# 6_Power_distribution_II.net
KiCad netlist of a schematic drawn in Altium Designer
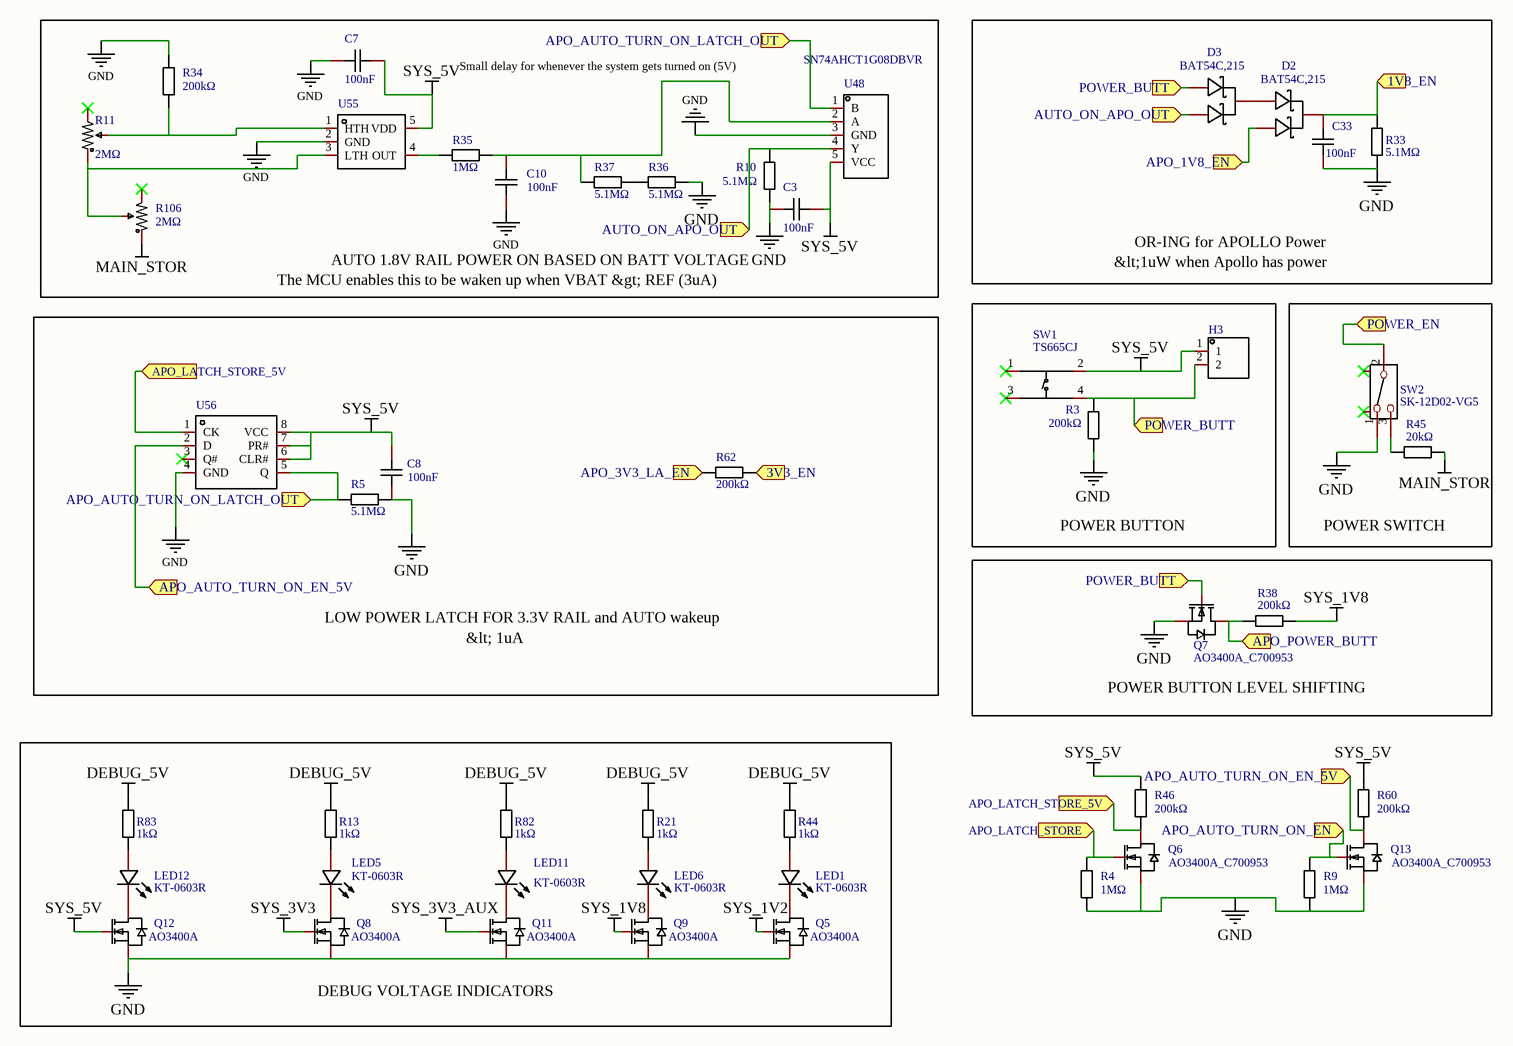
[diagram p0: 6_Power distribution II.schdoc]

(export (version "E")
  (design (tool "Eeschema 10.0.6"))
  (components
    (comp (ref "C3")
      (value "100nF")
      (fields
        (field (name "NAME") "100nF")
        (field (name "MANUFACTURER") "YAGEO")
        (field (name "MANUFACTURER PART") "CC0603KRX7R9BB104")
      )
      (libsource (lib "altium-import") (part "root_0_CC0603KRX7R9BB104_"))
    )
    (comp (ref "C7")
      (value "100nF")
      (fields
        (field (name "NAME") "100nF")
        (field (name "MANUFACTURER") "YAGEO")
        (field (name "MANUFACTURER PART") "CC0603KRX7R9BB104")
      )
      (libsource (lib "altium-import") (part "root_0_CC0603KRX7R9BB104_"))
    )
    (comp (ref "C8")
      (value "100nF")
      (fields
        (field (name "NAME") "100nF")
        (field (name "MANUFACTURER") "YAGEO")
        (field (name "MANUFACTURER PART") "CC0603KRX7R9BB104")
      )
      (libsource (lib "altium-import") (part "root_3_CC0603KRX7R9BB104_"))
    )
    (comp (ref "C10")
      (value "100nF")
      (fields
        (field (name "NAME") "100nF")
        (field (name "MANUFACTURER") "YAGEO")
        (field (name "MANUFACTURER PART") "CC0603KRX7R9BB104")
      )
      (libsource (lib "altium-import") (part "root_1_CC0603KRX7R9BB104_"))
    )
    (comp (ref "C33")
      (value "100nF")
      (fields
        (field (name "NAME") "100nF")
        (field (name "MANUFACTURER") "YAGEO")
        (field (name "MANUFACTURER PART") "CC0603KRX7R9BB104")
      )
      (libsource (lib "altium-import") (part "root_3_CC0603KRX7R9BB104_"))
    )
    (comp (ref "D2")
      (value "BAT54C,215")
      (fields (field (name "NAME") "BAT54C,215") (field (name "MANUFACTURER") "Nexperia"))
      (libsource (lib "altium-import") (part "root_0_BAT54C,215_"))
    )
    (comp (ref "D3")
      (value "BAT54C,215")
      (fields (field (name "NAME") "BAT54C,215") (field (name "MANUFACTURER") "Nexperia"))
      (libsource (lib "altium-import") (part "root_0_BAT54C,215_"))
    )
    (comp (ref "H3")
      (value "HDR-M_2.54_1x2P")
      (libsource (lib "altium-import") (part "root_0_HDR-M_2.54_1x2P_"))
    )
    (comp (ref "LED1")
      (value "KT-0603R")
      (fields (field (name "NAME") "KT-0603R") (field (name "MANUFACTURER") "KENTO"))
      (libsource (lib "altium-import") (part "root_1_KT-0603R_"))
    )
    (comp (ref "LED5")
      (value "KT-0603R")
      (fields (field (name "NAME") "KT-0603R") (field (name "MANUFACTURER") "KENTO"))
      (libsource (lib "altium-import") (part "root_1_KT-0603R_"))
    )
    (comp (ref "LED6")
      (value "KT-0603R")
      (fields (field (name "NAME") "KT-0603R") (field (name "MANUFACTURER") "KENTO"))
      (libsource (lib "altium-import") (part "root_1_KT-0603R_"))
    )
    (comp (ref "LED11")
      (value "KT-0603R")
      (fields (field (name "NAME") "KT-0603R") (field (name "MANUFACTURER") "KENTO"))
      (libsource (lib "altium-import") (part "root_1_KT-0603R_"))
    )
    (comp (ref "LED12")
      (value "KT-0603R")
      (fields (field (name "NAME") "KT-0603R") (field (name "MANUFACTURER") "KENTO"))
      (libsource (lib "altium-import") (part "root_1_KT-0603R_"))
    )
    (comp (ref "Q5")
      (value "AO3400A")
      (fields (field (name "NAME") "AO3400A") (field (name "MANUFACTURER") "HUASHUO(华朔)"))
      (libsource (lib "altium-import") (part "root_0_AO3400A_"))
    )
    (comp (ref "Q6")
      (value "AO3400A_C700953")
      (fields
        (field (name "NAME") "AO3400A_C700953")
        (field (name "MANUFACTURER") "HUASHUO(华朔)")
        (field (name "MANUFACTURER PART") "AO3400A")
      )
      (libsource (lib "altium-import") (part "root_0_AO3400A_"))
    )
    (comp (ref "Q7")
      (value "AO3400A_C700953")
      (fields
        (field (name "NAME") "AO3400A_C700953")
        (field (name "MANUFACTURER") "HUASHUO(华朔)")
        (field (name "MANUFACTURER PART") "AO3400A")
      )
      (libsource (lib "altium-import") (part "root_3_AO3400A_"))
    )
    (comp (ref "Q8")
      (value "AO3400A")
      (fields (field (name "NAME") "AO3400A") (field (name "MANUFACTURER") "HUASHUO(华朔)"))
      (libsource (lib "altium-import") (part "root_0_AO3400A_"))
    )
    (comp (ref "Q9")
      (value "AO3400A")
      (fields (field (name "NAME") "AO3400A") (field (name "MANUFACTURER") "HUASHUO(华朔)"))
      (libsource (lib "altium-import") (part "root_0_AO3400A_"))
    )
    (comp (ref "Q11")
      (value "AO3400A")
      (fields (field (name "NAME") "AO3400A") (field (name "MANUFACTURER") "HUASHUO(华朔)"))
      (libsource (lib "altium-import") (part "root_0_AO3400A_"))
    )
    (comp (ref "Q12")
      (value "AO3400A")
      (fields (field (name "NAME") "AO3400A") (field (name "MANUFACTURER") "HUASHUO(华朔)"))
      (libsource (lib "altium-import") (part "root_0_AO3400A_"))
    )
    (comp (ref "Q13")
      (value "AO3400A_C700953")
      (fields
        (field (name "NAME") "AO3400A_C700953")
        (field (name "MANUFACTURER") "HUASHUO(华朔)")
        (field (name "MANUFACTURER PART") "AO3400A")
      )
      (libsource (lib "altium-import") (part "root_0_AO3400A_"))
    )
    (comp (ref "R3")
      (value "200kΩ")
      (fields
        (field (name "NAME") "200kΩ")
        (field (name "MANUFACTURER") "UniOhm")
        (field (name "MANUFACTURER PART") "0603WAF2003T5E")
      )
      (libsource (lib "altium-import") (part "root_1_0603WAF2003T5E_"))
    )
    (comp (ref "R4")
      (value "1MΩ")
      (fields
        (field (name "NAME") "1MΩ")
        (field (name "MANUFACTURER") "UniOhm")
        (field (name "MANUFACTURER PART") "0603WAF1004T5E")
      )
      (libsource (lib "altium-import") (part "root_3_0603WAF1004T5E_"))
    )
    (comp (ref "R5")
      (value "5.1MΩ")
      (fields
        (field (name "NAME") "5.1MΩ")
        (field (name "MANUFACTURER") "UniOhm")
        (field (name "MANUFACTURER PART") "0603WAF5104T5E")
      )
      (libsource (lib "altium-import") (part "root_2_0603WAF5104T5E_"))
    )
    (comp (ref "R9")
      (value "1MΩ")
      (fields
        (field (name "NAME") "1MΩ")
        (field (name "MANUFACTURER") "UniOhm")
        (field (name "MANUFACTURER PART") "0603WAF1004T5E")
      )
      (libsource (lib "altium-import") (part "root_3_0603WAF1004T5E_"))
    )
    (comp (ref "R10")
      (value "5.1MΩ")
      (fields
        (field (name "NAME") "5.1MΩ")
        (field (name "MANUFACTURER") "UniOhm")
        (field (name "MANUFACTURER PART") "0603WAF5104T5E")
      )
      (libsource (lib "altium-import") (part "root_1_0603WAF5104T5E_"))
    )
    (comp (ref "R11")
      (value "2MΩ")
      (description "Resistance: Tolerance:±10% Tolerance:±10%")
      (fields (field (name "MANUFACTURER") "BOURNS") (field (name "MANUFACTURER PART") "3386P-1-205LF"))
      (libsource (lib "altium-import") (part "root_3_3386P-1-205LF_"))
    )
    (comp (ref "R13")
      (value "1kΩ")
      (fields
        (field (name "NAME") "1kΩ")
        (field (name "MANUFACTURER") "UniOhm")
        (field (name "MANUFACTURER PART") "0603WAF1001T5E")
      )
      (libsource (lib "altium-import") (part "root_1_0603WAF1001T5E_"))
    )
    (comp (ref "R21")
      (value "1kΩ")
      (fields
        (field (name "NAME") "1kΩ")
        (field (name "MANUFACTURER") "UniOhm")
        (field (name "MANUFACTURER PART") "0603WAF1001T5E")
      )
      (libsource (lib "altium-import") (part "root_1_0603WAF1001T5E_"))
    )
    (comp (ref "R33")
      (value "5.1MΩ")
      (fields
        (field (name "NAME") "5.1MΩ")
        (field (name "MANUFACTURER") "UniOhm")
        (field (name "MANUFACTURER PART") "0603WAF5104T5E")
      )
      (libsource (lib "altium-import") (part "root_1_0603WAF5104T5E_"))
    )
    (comp (ref "R34")
      (value "200kΩ")
      (fields
        (field (name "NAME") "200kΩ")
        (field (name "MANUFACTURER") "UniOhm")
        (field (name "MANUFACTURER PART") "0603WAF2003T5E")
      )
      (libsource (lib "altium-import") (part "root_3_0603WAF2003T5E_"))
    )
    (comp (ref "R35")
      (value "1MΩ")
      (fields
        (field (name "NAME") "1MΩ")
        (field (name "MANUFACTURER") "UniOhm")
        (field (name "MANUFACTURER PART") "0603WAF1004T5E")
      )
      (libsource (lib "altium-import") (part "root_2_0603WAF1004T5E_"))
    )
    (comp (ref "R36")
      (value "5.1MΩ")
      (fields
        (field (name "NAME") "5.1MΩ")
        (field (name "MANUFACTURER") "UniOhm")
        (field (name "MANUFACTURER PART") "0603WAF5104T5E")
      )
      (libsource (lib "altium-import") (part "root_2_0603WAF5104T5E_"))
    )
    (comp (ref "R37")
      (value "5.1MΩ")
      (fields
        (field (name "NAME") "5.1MΩ")
        (field (name "MANUFACTURER") "UniOhm")
        (field (name "MANUFACTURER PART") "0603WAF5104T5E")
      )
      (libsource (lib "altium-import") (part "root_2_0603WAF5104T5E_"))
    )
    (comp (ref "R38")
      (value "200kΩ")
      (fields
        (field (name "NAME") "200kΩ")
        (field (name "MANUFACTURER") "UniOhm")
        (field (name "MANUFACTURER PART") "0603WAF2003T5E")
      )
      (libsource (lib "altium-import") (part "root_2_0603WAF2003T5E_"))
    )
    (comp (ref "R44")
      (value "1kΩ")
      (fields
        (field (name "NAME") "1kΩ")
        (field (name "MANUFACTURER") "UniOhm")
        (field (name "MANUFACTURER PART") "0603WAF1001T5E")
      )
      (libsource (lib "altium-import") (part "root_1_0603WAF1001T5E_"))
    )
    (comp (ref "R45")
      (value "20kΩ")
      (fields
        (field (name "NAME") "20kΩ")
        (field (name "MANUFACTURER") "UniOhm")
        (field (name "MANUFACTURER PART") "0603WAF2002T5E")
      )
      (libsource (lib "altium-import") (part "root_2_0603WAF2002T5E_"))
    )
    (comp (ref "R46")
      (value "200kΩ")
      (fields
        (field (name "NAME") "200kΩ")
        (field (name "MANUFACTURER") "UniOhm")
        (field (name "MANUFACTURER PART") "0603WAF2003T5E")
      )
      (libsource (lib "altium-import") (part "root_3_0603WAF2003T5E_"))
    )
    (comp (ref "R60")
      (value "200kΩ")
      (fields
        (field (name "NAME") "200kΩ")
        (field (name "MANUFACTURER") "UniOhm")
        (field (name "MANUFACTURER PART") "0603WAF2003T5E")
      )
      (libsource (lib "altium-import") (part "root_3_0603WAF2003T5E_"))
    )
    (comp (ref "R62")
      (value "200kΩ")
      (fields
        (field (name "NAME") "200kΩ")
        (field (name "MANUFACTURER") "UniOhm")
        (field (name "MANUFACTURER PART") "0603WAF2003T5E")
      )
      (libsource (lib "altium-import") (part "root_0_0603WAF2003T5E_"))
    )
    (comp (ref "R82")
      (value "1kΩ")
      (fields
        (field (name "NAME") "1kΩ")
        (field (name "MANUFACTURER") "UniOhm")
        (field (name "MANUFACTURER PART") "0603WAF1001T5E")
      )
      (libsource (lib "altium-import") (part "root_1_0603WAF1001T5E_"))
    )
    (comp (ref "R83")
      (value "1kΩ")
      (fields
        (field (name "NAME") "1kΩ")
        (field (name "MANUFACTURER") "UniOhm")
        (field (name "MANUFACTURER PART") "0603WAF1001T5E")
      )
      (libsource (lib "altium-import") (part "root_1_0603WAF1001T5E_"))
    )
    (comp (ref "R106")
      (value "2MΩ")
      (description "Resistance: Tolerance:±10% Tolerance:±10%")
      (fields (field (name "MANUFACTURER") "BOURNS") (field (name "MANUFACTURER PART") "3386P-1-205LF"))
      (libsource (lib "altium-import") (part "root_3_mirrored_3386P-1-205LF_"))
    )
    (comp (ref "SW1")
      (value "TS665CJ")
      (fields (field (name "NAME") "TS665CJ") (field (name "MANUFACTURER") "SHOU HAN"))
      (libsource (lib "altium-import") (part "root_0_TS665CJ_"))
    )
    (comp (ref "SW2")
      (value "SK-12D02-VG5")
      (fields
        (field (name "NAME") "SK-12D02-VG5")
        (field (name "MANUFACTURER") "Rectangular Connectors - Contacts")
      )
      (libsource (lib "altium-import") (part "root_3_SK-12D02-VG5_"))
    )
    (comp (ref "U48")
      (value "SN74AHCT1G08DBVR_C113521")
      (fields (field (name "MANUFACTURER") "TI(德州仪器)") (field (name "MANUFACTURER PART") "SN74AHCT1G08DBVR"))
      (libsource (lib "altium-import") (part "root_0_SN74AHCT1G08DBVR_C113521_"))
    )
    (comp (ref "U55")
      (value "MIC841HYC5-TR")
      (fields (field (name "MANUFACTURER") "MICROCHIP(美国微芯)"))
      (libsource (lib "altium-import") (part "root_0_MIC841HYC5-TR_"))
    )
    (comp (ref "U56")
      (value "TC7W74FU,LF")
      (fields (field (name "MANUFACTURER") "TOSHIBA(东芝)"))
      (libsource (lib "altium-import") (part "root_0_TC7W74FU,LF_"))
    )
  )
  (nets
    (net (code "1") (name "/1V8_EN") (class "Default")
      (node (ref "C33") (pin "1") (pinfunction "1_1") (pintype "passive"))
      (node (ref "D2") (pin "3") (pinfunction "K_3") (pintype "passive"))
      (node (ref "R33") (pin "1") (pinfunction "1_1") (pintype "passive"))
    )
    (net (code "2") (name "/3V3_EN") (class "Default")
      (node (ref "R62") (pin "2") (pinfunction "2_2") (pintype "passive"))
    )
    (net (code "3") (name "/APO_1V8_EN") (class "Default")
      (node (ref "D2") (pin "2") (pinfunction "A_2") (pintype "passive"))
    )
    (net (code "4") (name "/APO_3V3_LA_EN") (class "Default")
      (node (ref "R62") (pin "1") (pinfunction "1_1") (pintype "passive"))
    )
    (net (code "5") (name "/APO_AUTO_TURN_ON_EN") (class "Default")
      (node (ref "Q13") (pin "1") (pinfunction "G_1") (pintype "passive"))
      (node (ref "R9") (pin "1") (pinfunction "1_1") (pintype "passive"))
    )
    (net (code "6") (name "/APO_AUTO_TURN_ON_EN_5V") (class "Default")
      (node (ref "Q13") (pin "3") (pinfunction "D_3") (pintype "passive"))
      (node (ref "R60") (pin "2") (pinfunction "2_2") (pintype "passive"))
      (node (ref "U56") (pin "2") (pinfunction "D_2") (pintype "passive"))
    )
    (net (code "7") (name "/APO_AUTO_TURN_ON_LATCH_OUT") (class "Default")
      (node (ref "R5") (pin "1") (pinfunction "1_1") (pintype "passive"))
      (node (ref "U48") (pin "1") (pinfunction "B_1") (pintype "passive"))
      (node (ref "U56") (pin "5") (pinfunction "Q_5") (pintype "passive"))
    )
    (net (code "8") (name "/APO_LATCH_STORE") (class "Default")
      (node (ref "Q6") (pin "1") (pinfunction "G_1") (pintype "passive"))
      (node (ref "R4") (pin "1") (pinfunction "1_1") (pintype "passive"))
    )
    (net (code "9") (name "/APO_LATCH_STORE_5V") (class "Default")
      (node (ref "Q6") (pin "3") (pinfunction "D_3") (pintype "passive"))
      (node (ref "R46") (pin "2") (pinfunction "2_2") (pintype "passive"))
      (node (ref "U56") (pin "1") (pinfunction "CK_1") (pintype "passive"))
    )
    (net (code "10") (name "/APO_POWER_BUTT") (class "Default")
      (node (ref "Q7") (pin "3") (pinfunction "D_3") (pintype "passive"))
      (node (ref "R38") (pin "2") (pinfunction "2_2") (pintype "passive"))
    )
    (net (code "11") (name "/AUTO_ON_APO_OUT") (class "Default")
      (node (ref "D3") (pin "2") (pinfunction "A_2") (pintype "passive"))
      (node (ref "R10") (pin "1") (pinfunction "1_1") (pintype "passive"))
      (node (ref "U48") (pin "4") (pinfunction "Y_4") (pintype "passive"))
    )
    (net (code "12") (name "/POWER_BUTT") (class "Default")
      (node (ref "D3") (pin "1") (pinfunction "A_1") (pintype "passive"))
      (node (ref "H3") (pin "2") (pinfunction "2_2") (pintype "passive"))
      (node (ref "Q7") (pin "1") (pinfunction "G_1") (pintype "passive"))
      (node (ref "R3") (pin "2") (pinfunction "2_2") (pintype "passive"))
      (node (ref "SW1") (pin "4") (pinfunction "D_4") (pintype "passive"))
    )
    (net (code "13") (name "/POWER_EN") (class "Default")
      (node (ref "SW2") (pin "2") (pinfunction "2_2") (pintype "passive"))
    )
    (net (code "14") (name "DEBUG_5V") (class "Default")
      (node (ref "R13") (pin "2") (pinfunction "2_2") (pintype "passive"))
      (node (ref "R21") (pin "2") (pinfunction "2_2") (pintype "passive"))
      (node (ref "R44") (pin "2") (pinfunction "2_2") (pintype "passive"))
      (node (ref "R82") (pin "2") (pinfunction "2_2") (pintype "passive"))
      (node (ref "R83") (pin "2") (pinfunction "2_2") (pintype "passive"))
    )
    (net (code "15") (name "GND") (class "Default")
      (node (ref "C10") (pin "1") (pinfunction "1_1") (pintype "passive"))
      (node (ref "C3") (pin "1") (pinfunction "1_1") (pintype "passive"))
      (node (ref "C33") (pin "2") (pinfunction "2_2") (pintype "passive"))
      (node (ref "C7") (pin "1") (pinfunction "1_1") (pintype "passive"))
      (node (ref "C8") (pin "2") (pinfunction "2_2") (pintype "passive"))
      (node (ref "Q11") (pin "2") (pinfunction "S_2") (pintype "passive"))
      (node (ref "Q12") (pin "2") (pinfunction "S_2") (pintype "passive"))
      (node (ref "Q13") (pin "2") (pinfunction "S_2") (pintype "passive"))
      (node (ref "Q5") (pin "2") (pinfunction "S_2") (pintype "passive"))
      (node (ref "Q6") (pin "2") (pinfunction "S_2") (pintype "passive"))
      (node (ref "Q7") (pin "2") (pinfunction "S_2") (pintype "passive"))
      (node (ref "Q8") (pin "2") (pinfunction "S_2") (pintype "passive"))
      (node (ref "Q9") (pin "2") (pinfunction "S_2") (pintype "passive"))
      (node (ref "R10") (pin "2") (pinfunction "2_2") (pintype "passive"))
      (node (ref "R3") (pin "1") (pinfunction "1_1") (pintype "passive"))
      (node (ref "R33") (pin "2") (pinfunction "2_2") (pintype "passive"))
      (node (ref "R34") (pin "1") (pinfunction "1_1") (pintype "passive"))
      (node (ref "R36") (pin "2") (pinfunction "2_2") (pintype "passive"))
      (node (ref "R4") (pin "2") (pinfunction "2_2") (pintype "passive"))
      (node (ref "R5") (pin "2") (pinfunction "2_2") (pintype "passive"))
      (node (ref "R9") (pin "2") (pinfunction "2_2") (pintype "passive"))
      (node (ref "SW2") (pin "1") (pinfunction "1_1") (pintype "passive"))
      (node (ref "U48") (pin "3") (pinfunction "GND_3") (pintype "passive"))
      (node (ref "U55") (pin "2") (pinfunction "GND_2") (pintype "passive"))
      (node (ref "U56") (pin "4") (pinfunction "GND_4") (pintype "passive"))
    )
    (net (code "16") (name "MAIN_STOR") (class "Default")
      (node (ref "R106") (pin "1") (pinfunction "1_1") (pintype "passive"))
      (node (ref "R45") (pin "1") (pinfunction "1_1") (pintype "passive"))
    )
    (net (code "17") (name "Net-(D3-K)") (class "Default")
      (node (ref "D2") (pin "1") (pinfunction "A_1") (pintype "passive"))
      (node (ref "D3") (pin "3") (pinfunction "K_3") (pintype "passive"))
    )
    (net (code "18") (name "Net-(LED1-A)") (class "Default")
      (node (ref "LED1") (pin "1") (pinfunction "A_1") (pintype "passive"))
      (node (ref "R44") (pin "1") (pinfunction "1_1") (pintype "passive"))
    )
    (net (code "19") (name "Net-(LED1-K)") (class "Default")
      (node (ref "LED1") (pin "2") (pinfunction "K_2") (pintype "passive"))
      (node (ref "Q5") (pin "3") (pinfunction "D_3") (pintype "passive"))
    )
    (net (code "20") (name "Net-(LED5-A)") (class "Default")
      (node (ref "LED5") (pin "1") (pinfunction "A_1") (pintype "passive"))
      (node (ref "R13") (pin "1") (pinfunction "1_1") (pintype "passive"))
    )
    (net (code "21") (name "Net-(LED5-K)") (class "Default")
      (node (ref "LED5") (pin "2") (pinfunction "K_2") (pintype "passive"))
      (node (ref "Q8") (pin "3") (pinfunction "D_3") (pintype "passive"))
    )
    (net (code "22") (name "Net-(LED6-A)") (class "Default")
      (node (ref "LED6") (pin "1") (pinfunction "A_1") (pintype "passive"))
      (node (ref "R21") (pin "1") (pinfunction "1_1") (pintype "passive"))
    )
    (net (code "23") (name "Net-(LED6-K)") (class "Default")
      (node (ref "LED6") (pin "2") (pinfunction "K_2") (pintype "passive"))
      (node (ref "Q9") (pin "3") (pinfunction "D_3") (pintype "passive"))
    )
    (net (code "24") (name "Net-(LED11-A)") (class "Default")
      (node (ref "LED11") (pin "1") (pinfunction "A_1") (pintype "passive"))
      (node (ref "R82") (pin "1") (pinfunction "1_1") (pintype "passive"))
    )
    (net (code "25") (name "Net-(LED11-K)") (class "Default")
      (node (ref "LED11") (pin "2") (pinfunction "K_2") (pintype "passive"))
      (node (ref "Q11") (pin "3") (pinfunction "D_3") (pintype "passive"))
    )
    (net (code "26") (name "Net-(LED12-A)") (class "Default")
      (node (ref "LED12") (pin "1") (pinfunction "A_1") (pintype "passive"))
      (node (ref "R83") (pin "1") (pinfunction "1_1") (pintype "passive"))
    )
    (net (code "27") (name "Net-(LED12-K)") (class "Default")
      (node (ref "LED12") (pin "2") (pinfunction "K_2") (pintype "passive"))
      (node (ref "Q12") (pin "3") (pinfunction "D_3") (pintype "passive"))
    )
    (net (code "28") (name "Net-(R36-Pad1)") (class "Default")
      (node (ref "R36") (pin "1") (pinfunction "1_1") (pintype "passive"))
      (node (ref "R37") (pin "2") (pinfunction "2_2") (pintype "passive"))
    )
    (net (code "29") (name "Net-(R45-Pad2)") (class "Default")
      (node (ref "R45") (pin "2") (pinfunction "2_2") (pintype "passive"))
      (node (ref "SW2") (pin "3") (pinfunction "3_3") (pintype "passive"))
    )
    (net (code "30") (name "Net-(U48-A)") (class "Default")
      (node (ref "C10") (pin "2") (pinfunction "2_2") (pintype "passive"))
      (node (ref "R35") (pin "1") (pinfunction "1_1") (pintype "passive"))
      (node (ref "R37") (pin "1") (pinfunction "1_1") (pintype "passive"))
      (node (ref "U48") (pin "2") (pinfunction "A_2") (pintype "passive"))
    )
    (net (code "31") (name "Net-(U55-HTH)") (class "Default")
      (node (ref "R11") (pin "2") (pinfunction "2_2") (pintype "passive"))
      (node (ref "R34") (pin "2") (pinfunction "2_2") (pintype "passive"))
      (node (ref "U55") (pin "1") (pinfunction "HTH_1") (pintype "passive"))
    )
    (net (code "32") (name "Net-(U55-LTH)") (class "Default")
      (node (ref "R106") (pin "2") (pinfunction "2_2") (pintype "passive"))
      (node (ref "R11") (pin "1") (pinfunction "1_1") (pintype "passive"))
      (node (ref "U55") (pin "3") (pinfunction "LTH_3") (pintype "passive"))
    )
    (net (code "33") (name "Net-(U55-OUT)") (class "Default")
      (node (ref "R35") (pin "2") (pinfunction "2_2") (pintype "passive"))
      (node (ref "U55") (pin "4") (pinfunction "OUT_4") (pintype "passive"))
    )
    (net (code "34") (name "SYS_1V2") (class "Default")
      (node (ref "Q5") (pin "1") (pinfunction "G_1") (pintype "passive"))
    )
    (net (code "35") (name "SYS_1V8") (class "Default")
      (node (ref "Q9") (pin "1") (pinfunction "G_1") (pintype "passive"))
      (node (ref "R38") (pin "1") (pinfunction "1_1") (pintype "passive"))
    )
    (net (code "36") (name "SYS_3V3") (class "Default")
      (node (ref "Q8") (pin "1") (pinfunction "G_1") (pintype "passive"))
    )
    (net (code "37") (name "SYS_3V3_AUX") (class "Default")
      (node (ref "Q11") (pin "1") (pinfunction "G_1") (pintype "passive"))
    )
    (net (code "38") (name "SYS_5V") (class "Default")
      (node (ref "C3") (pin "2") (pinfunction "2_2") (pintype "passive"))
      (node (ref "C7") (pin "2") (pinfunction "2_2") (pintype "passive"))
      (node (ref "C8") (pin "1") (pinfunction "1_1") (pintype "passive"))
      (node (ref "H3") (pin "1") (pinfunction "1_1") (pintype "passive"))
      (node (ref "Q12") (pin "1") (pinfunction "G_1") (pintype "passive"))
      (node (ref "R46") (pin "1") (pinfunction "1_1") (pintype "passive"))
      (node (ref "R60") (pin "1") (pinfunction "1_1") (pintype "passive"))
      (node (ref "SW1") (pin "2") (pinfunction "B_2") (pintype "passive"))
      (node (ref "U48") (pin "5") (pinfunction "VCC_5") (pintype "passive"))
      (node (ref "U55") (pin "5") (pinfunction "VDD_5") (pintype "passive"))
      (node (ref "U56") (pin "6") (pinfunction "CLR#_6") (pintype "passive"))
      (node (ref "U56") (pin "7") (pinfunction "PR#_7") (pintype "passive"))
      (node (ref "U56") (pin "8") (pinfunction "VCC_8") (pintype "passive"))
    )
    (net (code "39") (name "unconnected-(R11-Pad3)") (class "Default")
      (node (ref "R11") (pin "3") (pinfunction "3_3") (pintype "passive+no_connect"))
    )
    (net (code "40") (name "unconnected-(R106-Pad3)") (class "Default")
      (node (ref "R106") (pin "3") (pinfunction "3_3") (pintype "passive+no_connect"))
    )
    (net (code "41") (name "unconnected-(SW1-A-Pad1)") (class "Default")
      (node (ref "SW1") (pin "1") (pinfunction "A_1") (pintype "passive+no_connect"))
    )
    (net (code "42") (name "unconnected-(SW1-C-Pad3)") (class "Default")
      (node (ref "SW1") (pin "3") (pinfunction "C_3") (pintype "passive+no_connect"))
    )
    (net (code "43") (name "unconnected-(SW2-Pad4)") (class "Default")
      (node (ref "SW2") (pin "4") (pinfunction "4_4") (pintype "passive+no_connect"))
    )
    (net (code "44") (name "unconnected-(SW2-Pad5)") (class "Default")
      (node (ref "SW2") (pin "5") (pinfunction "5_5") (pintype "passive+no_connect"))
    )
    (net (code "45") (name "unconnected-(U56-Q#-Pad3)") (class "Default")
      (node (ref "U56") (pin "3") (pinfunction "Q#_3") (pintype "passive+no_connect"))
    )
  )
)
